# tx.net
KiCad netlist of a schematic drawn in Altium Designer
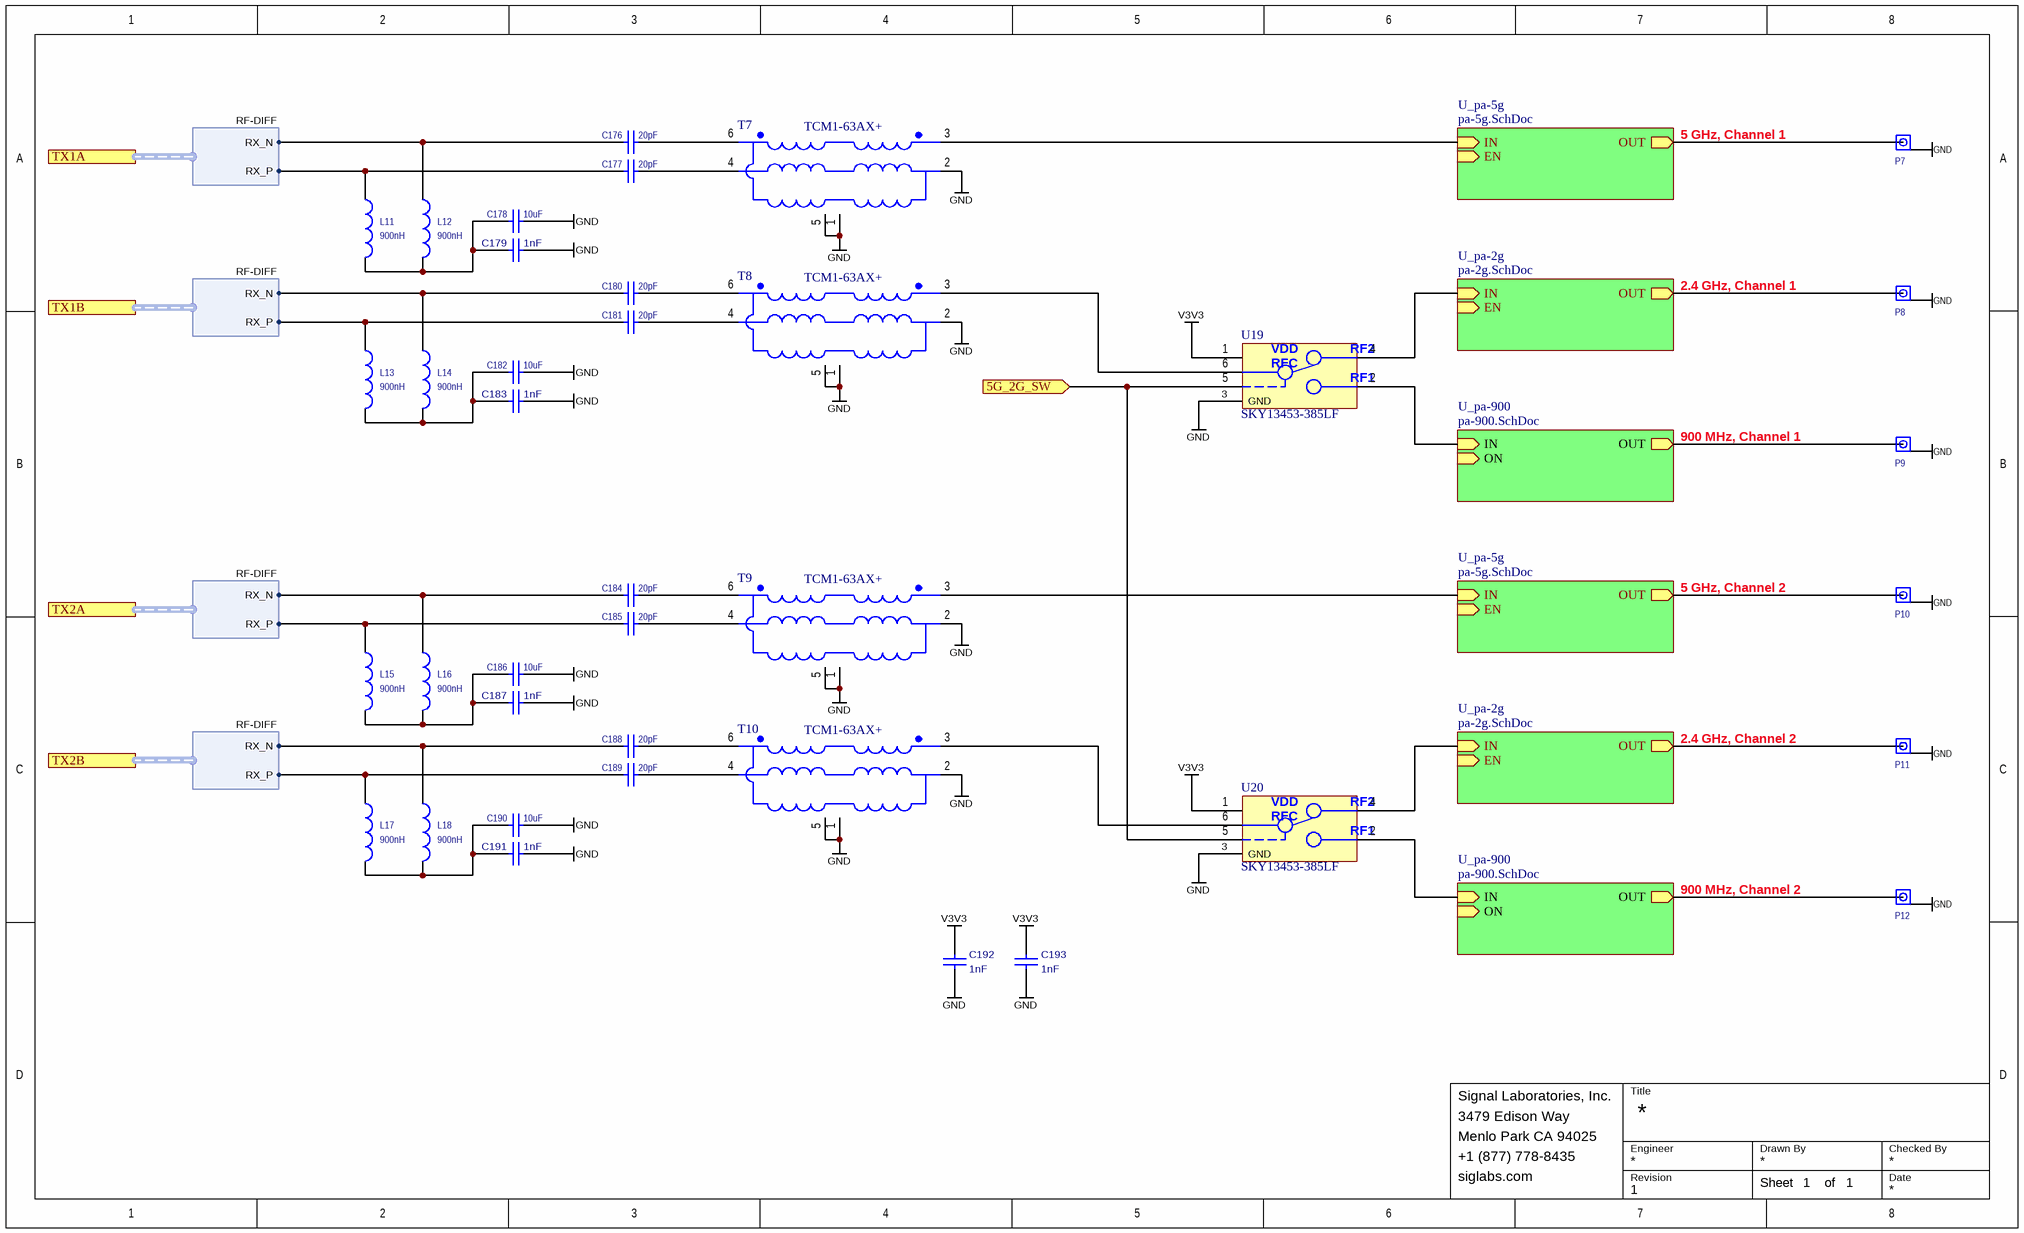
[diagram p0: tx.SchDoc]

(export (version "E")
  (design (tool "Eeschema 10.0.6"))
  (components
    (comp (ref "C176")
      (value "20pF")
      (footprint "generic:0402")
      (description "Ceramic Capacitor 20pF ±1% 50V NP0 0402")
      (fields (field (name "VOLTAGE") "50V") (field (name "MANUFACTURER") "Kemet"))
      (libsource (lib "PopRock") (part "CAP 0402"))
    )
    (comp (ref "C177")
      (value "20pF")
      (footprint "generic:0402")
      (description "Ceramic Capacitor 20pF ±1% 50V NP0 0402")
      (fields (field (name "VOLTAGE") "50V") (field (name "MANUFACTURER") "Kemet"))
      (libsource (lib "PopRock") (part "CAP 0402"))
    )
    (comp (ref "C178")
      (value "10uF")
      (footprint "generic:0603")
      (description "Ceramic Capacitor 10uF ±20% 25V X5R 0603")
      (fields (field (name "MANUFACTURER") "Samsung") (field (name "VOLTAGE") "25V"))
      (libsource (lib "generic") (part "CAP 0603"))
    )
    (comp (ref "C179")
      (value "1nF")
      (footprint "CAPC160X80X90L20N")
      (description "Ceramic Capacitor 1nF ±10% 50V X7R 0402")
      (fields (field (name "MANUFACTURER") "Vishay") (field (name "TOLERANCE") "±10%"))
      (libsource (lib "capacitors") (part "CAP"))
    )
    (comp (ref "C180")
      (value "20pF")
      (footprint "generic:0402")
      (description "Ceramic Capacitor 20pF ±1% 50V NP0 0402")
      (fields (field (name "VOLTAGE") "50V") (field (name "MANUFACTURER") "Kemet"))
      (libsource (lib "PopRock") (part "CAP 0402"))
    )
    (comp (ref "C181")
      (value "20pF")
      (footprint "generic:0402")
      (description "Ceramic Capacitor 20pF ±1% 50V NP0 0402")
      (fields (field (name "VOLTAGE") "50V") (field (name "MANUFACTURER") "Kemet"))
      (libsource (lib "PopRock") (part "CAP 0402"))
    )
    (comp (ref "C182")
      (value "10uF")
      (footprint "generic:0603")
      (description "Ceramic Capacitor 10uF ±20% 25V X5R 0603")
      (fields (field (name "MANUFACTURER") "Samsung") (field (name "VOLTAGE") "25V"))
      (libsource (lib "generic") (part "CAP 0603"))
    )
    (comp (ref "C183")
      (value "1nF")
      (footprint "CAPC160X80X90L20N")
      (description "Ceramic Capacitor 1nF ±10% 50V X7R 0402")
      (fields (field (name "MANUFACTURER") "Vishay") (field (name "TOLERANCE") "±10%"))
      (libsource (lib "capacitors") (part "CAP"))
    )
    (comp (ref "C184")
      (value "20pF")
      (footprint "generic:0402")
      (description "Ceramic Capacitor 20pF ±1% 50V NP0 0402")
      (fields (field (name "VOLTAGE") "50V") (field (name "MANUFACTURER") "Kemet"))
      (libsource (lib "PopRock") (part "CAP 0402"))
    )
    (comp (ref "C185")
      (value "20pF")
      (footprint "generic:0402")
      (description "Ceramic Capacitor 20pF ±1% 50V NP0 0402")
      (fields (field (name "VOLTAGE") "50V") (field (name "MANUFACTURER") "Kemet"))
      (libsource (lib "PopRock") (part "CAP 0402"))
    )
    (comp (ref "C186")
      (value "10uF")
      (footprint "generic:0603")
      (description "Ceramic Capacitor 10uF ±20% 25V X5R 0603")
      (fields (field (name "MANUFACTURER") "Samsung") (field (name "VOLTAGE") "25V"))
      (libsource (lib "generic") (part "CAP 0603"))
    )
    (comp (ref "C187")
      (value "1nF")
      (footprint "CAPC160X80X90L20N")
      (description "Ceramic Capacitor 1nF ±10% 50V X7R 0402")
      (fields (field (name "MANUFACTURER") "Vishay") (field (name "TOLERANCE") "±10%"))
      (libsource (lib "capacitors") (part "CAP"))
    )
    (comp (ref "C188")
      (value "20pF")
      (footprint "generic:0402")
      (description "Ceramic Capacitor 20pF ±1% 50V NP0 0402")
      (fields (field (name "VOLTAGE") "50V") (field (name "MANUFACTURER") "Kemet"))
      (libsource (lib "PopRock") (part "CAP 0402"))
    )
    (comp (ref "C189")
      (value "20pF")
      (footprint "generic:0402")
      (description "Ceramic Capacitor 20pF ±1% 50V NP0 0402")
      (fields (field (name "VOLTAGE") "50V") (field (name "MANUFACTURER") "Kemet"))
      (libsource (lib "PopRock") (part "CAP 0402"))
    )
    (comp (ref "C190")
      (value "10uF")
      (footprint "generic:0603")
      (description "Ceramic Capacitor 10uF ±20% 25V X5R 0603")
      (fields (field (name "MANUFACTURER") "Samsung") (field (name "VOLTAGE") "25V"))
      (libsource (lib "generic") (part "CAP 0603"))
    )
    (comp (ref "C191")
      (value "1nF")
      (footprint "CAPC160X80X90L20N")
      (description "Ceramic Capacitor 1nF ±10% 50V X7R 0402")
      (fields (field (name "MANUFACTURER") "Vishay") (field (name "TOLERANCE") "±10%"))
      (libsource (lib "capacitors") (part "CAP"))
    )
    (comp (ref "C192")
      (value "1nF")
      (footprint "CAPC160X80X90L20N")
      (description "Ceramic Capacitor 1nF ±10% 50V X7R 0402")
      (fields (field (name "MANUFACTURER") "Vishay") (field (name "TOLERANCE") "±10%"))
      (libsource (lib "capacitors") (part "CAP"))
    )
    (comp (ref "C193")
      (value "1nF")
      (footprint "CAPC160X80X90L20N")
      (description "Ceramic Capacitor 1nF ±10% 50V X7R 0402")
      (fields (field (name "MANUFACTURER") "Vishay") (field (name "TOLERANCE") "±10%"))
      (libsource (lib "capacitors") (part "CAP"))
    )
    (comp (ref "L11")
      (value "900nH")
      (footprint "coilcraft:COILCRAFT_1008AF")
      (description "Chip Inductor 900nH ±5% 1008")
      (fields (field (name "MANUFACTURER") "Coilcraft") (field (name "TOLERANCE") "±5%"))
      (libsource (lib "generic") (part "INDUCTOR"))
    )
    (comp (ref "L12")
      (value "900nH")
      (footprint "coilcraft:COILCRAFT_1008AF")
      (description "Chip Inductor 900nH ±5% 1008")
      (fields (field (name "MANUFACTURER") "Coilcraft") (field (name "TOLERANCE") "±5%"))
      (libsource (lib "generic") (part "INDUCTOR"))
    )
    (comp (ref "L13")
      (value "900nH")
      (footprint "coilcraft:COILCRAFT_1008AF")
      (description "Chip Inductor 900nH ±5% 1008")
      (fields (field (name "MANUFACTURER") "Coilcraft") (field (name "TOLERANCE") "±5%"))
      (libsource (lib "generic") (part "INDUCTOR"))
    )
    (comp (ref "L14")
      (value "900nH")
      (footprint "coilcraft:COILCRAFT_1008AF")
      (description "Chip Inductor 900nH ±5% 1008")
      (fields (field (name "MANUFACTURER") "Coilcraft") (field (name "TOLERANCE") "±5%"))
      (libsource (lib "generic") (part "INDUCTOR"))
    )
    (comp (ref "L15")
      (value "900nH")
      (footprint "coilcraft:COILCRAFT_1008AF")
      (description "Chip Inductor 900nH ±5% 1008")
      (fields (field (name "MANUFACTURER") "Coilcraft") (field (name "TOLERANCE") "±5%"))
      (libsource (lib "generic") (part "INDUCTOR"))
    )
    (comp (ref "L16")
      (value "900nH")
      (footprint "coilcraft:COILCRAFT_1008AF")
      (description "Chip Inductor 900nH ±5% 1008")
      (fields (field (name "MANUFACTURER") "Coilcraft") (field (name "TOLERANCE") "±5%"))
      (libsource (lib "generic") (part "INDUCTOR"))
    )
    (comp (ref "L17")
      (value "900nH")
      (footprint "coilcraft:COILCRAFT_1008AF")
      (description "Chip Inductor 900nH ±5% 1008")
      (fields (field (name "MANUFACTURER") "Coilcraft") (field (name "TOLERANCE") "±5%"))
      (libsource (lib "generic") (part "INDUCTOR"))
    )
    (comp (ref "L18")
      (value "900nH")
      (footprint "coilcraft:COILCRAFT_1008AF")
      (description "Chip Inductor 900nH ±5% 1008")
      (fields (field (name "MANUFACTURER") "Coilcraft") (field (name "TOLERANCE") "±5%"))
      (libsource (lib "generic") (part "INDUCTOR"))
    )
    (comp (ref "P7")
      (value "U.FL-R-SMT(10)")
      (footprint "U.FL-R-SMT(10)")
      (description "Ultra Miniature Coaxial Jack, 50 Ohms")
      (fields (field (name "MANUFACTURER") "Hirose"))
      (libsource (lib "hirose") (part "U.FL-R-SMT(10)"))
    )
    (comp (ref "P8")
      (value "U.FL-R-SMT(10)")
      (footprint "U.FL-R-SMT(10)")
      (description "Ultra Miniature Coaxial Jack, 50 Ohms")
      (fields (field (name "MANUFACTURER") "Hirose"))
      (libsource (lib "hirose") (part "U.FL-R-SMT(10)"))
    )
    (comp (ref "P9")
      (value "U.FL-R-SMT(10)")
      (footprint "U.FL-R-SMT(10)")
      (description "Ultra Miniature Coaxial Jack, 50 Ohms")
      (fields (field (name "MANUFACTURER") "Hirose"))
      (libsource (lib "hirose") (part "U.FL-R-SMT(10)"))
    )
    (comp (ref "P10")
      (value "U.FL-R-SMT(10)")
      (footprint "U.FL-R-SMT(10)")
      (description "Ultra Miniature Coaxial Jack, 50 Ohms")
      (fields (field (name "MANUFACTURER") "Hirose"))
      (libsource (lib "hirose") (part "U.FL-R-SMT(10)"))
    )
    (comp (ref "P11")
      (value "U.FL-R-SMT(10)")
      (footprint "U.FL-R-SMT(10)")
      (description "Ultra Miniature Coaxial Jack, 50 Ohms")
      (fields (field (name "MANUFACTURER") "Hirose"))
      (libsource (lib "hirose") (part "U.FL-R-SMT(10)"))
    )
    (comp (ref "P12")
      (value "U.FL-R-SMT(10)")
      (footprint "U.FL-R-SMT(10)")
      (description "Ultra Miniature Coaxial Jack, 50 Ohms")
      (fields (field (name "MANUFACTURER") "Hirose"))
      (libsource (lib "hirose") (part "U.FL-R-SMT(10)"))
    )
    (comp (ref "T7")
      (value "TCM1-63AX+")
      (footprint "TCM1-63AX+")
      (description "RF Transformer 10-6000KHz")
      (fields (field (name "MANUFACTURER") "Mini-Circuits"))
      (libsource (lib "Mini-Circuits") (part "TCM1-63AX+"))
    )
    (comp (ref "T8")
      (value "TCM1-63AX+")
      (footprint "TCM1-63AX+")
      (description "RF Transformer 10-6000KHz")
      (fields (field (name "MANUFACTURER") "Mini-Circuits"))
      (libsource (lib "Mini-Circuits") (part "TCM1-63AX+"))
    )
    (comp (ref "T9")
      (value "TCM1-63AX+")
      (footprint "TCM1-63AX+")
      (description "RF Transformer 10-6000KHz")
      (fields (field (name "MANUFACTURER") "Mini-Circuits"))
      (libsource (lib "Mini-Circuits") (part "TCM1-63AX+"))
    )
    (comp (ref "T10")
      (value "TCM1-63AX+")
      (footprint "TCM1-63AX+")
      (description "RF Transformer 10-6000KHz")
      (fields (field (name "MANUFACTURER") "Mini-Circuits"))
      (libsource (lib "Mini-Circuits") (part "TCM1-63AX+"))
    )
    (comp (ref "U19")
      (value "SKY13453-385LF")
      (footprint "SKY13453-385LF")
      (description "0.01 MHz-6.0 GHz RF SPDT Switch")
      (fields (field (name "MANUFACTURER") "Skyworks"))
      (libsource (lib "skyworks") (part "SKY13453-385LF"))
    )
    (comp (ref "U20")
      (value "SKY13453-385LF")
      (footprint "SKY13453-385LF")
      (description "0.01 MHz-6.0 GHz RF SPDT Switch")
      (fields (field (name "MANUFACTURER") "Skyworks"))
      (libsource (lib "skyworks") (part "SKY13453-385LF"))
    )
  )
  (nets
    (net (code "2") (name "/5G_2G_SW") (class "Default")
      (node (ref "U19") (pin "5") (pinfunction "CTL_5") (pintype "passive"))
      (node (ref "U20") (pin "5") (pinfunction "CTL_5") (pintype "passive"))
    )
    (net (code "7") (name "/IN") (class "Default")
      (node (ref "U20") (pin "4") (pinfunction "RF2_4") (pintype "passive"))
    )
    (net (code "8") (name "/IN_1") (class "Default")
      (node (ref "U20") (pin "2") (pinfunction "RF1_2") (pintype "passive"))
    )
    (net (code "9") (name "/IN_2") (class "Default")
      (node (ref "T7") (pin "3") (pinfunction "3_3") (pintype "passive"))
    )
    (net (code "10") (name "/IN_3") (class "Default")
      (node (ref "U19") (pin "4") (pinfunction "RF2_4") (pintype "passive"))
    )
    (net (code "11") (name "/IN_4") (class "Default")
      (node (ref "U19") (pin "2") (pinfunction "RF1_2") (pintype "passive"))
    )
    (net (code "12") (name "/IN_5") (class "Default")
      (node (ref "T9") (pin "3") (pinfunction "3_3") (pintype "passive"))
    )
    (net (code "15") (name "/OUT") (class "Default")
      (node (ref "P11") (pin "1") (pinfunction "RF_1") (pintype "passive"))
    )
    (net (code "16") (name "/OUT_1") (class "Default")
      (node (ref "P12") (pin "1") (pinfunction "RF_1") (pintype "passive"))
    )
    (net (code "17") (name "/OUT_2") (class "Default")
      (node (ref "P10") (pin "1") (pinfunction "RF_1") (pintype "passive"))
    )
    (net (code "18") (name "/OUT_3") (class "Default")
      (node (ref "P9") (pin "1") (pinfunction "RF_1") (pintype "passive"))
    )
    (net (code "19") (name "/OUT_4") (class "Default")
      (node (ref "P8") (pin "1") (pinfunction "RF_1") (pintype "passive"))
    )
    (net (code "20") (name "/OUT_5") (class "Default")
      (node (ref "P7") (pin "1") (pinfunction "RF_1") (pintype "passive"))
    )
    (net (code "22") (name "GND") (class "Default")
      (node (ref "C178") (pin "1") (pinfunction "1_1") (pintype "passive"))
      (node (ref "C179") (pin "2") (pinfunction "2_2") (pintype "passive"))
      (node (ref "C182") (pin "1") (pinfunction "1_1") (pintype "passive"))
      (node (ref "C183") (pin "2") (pinfunction "2_2") (pintype "passive"))
      (node (ref "C186") (pin "1") (pinfunction "1_1") (pintype "passive"))
      (node (ref "C187") (pin "2") (pinfunction "2_2") (pintype "passive"))
      (node (ref "C190") (pin "1") (pinfunction "1_1") (pintype "passive"))
      (node (ref "C191") (pin "2") (pinfunction "2_2") (pintype "passive"))
      (node (ref "C192") (pin "1") (pinfunction "1_1") (pintype "passive"))
      (node (ref "C193") (pin "1") (pinfunction "1_1") (pintype "passive"))
      (node (ref "P10") (pin "2") (pinfunction "GND_2") (pintype "passive"))
      (node (ref "P11") (pin "2") (pinfunction "GND_2") (pintype "passive"))
      (node (ref "P12") (pin "2") (pinfunction "GND_2") (pintype "passive"))
      (node (ref "P7") (pin "2") (pinfunction "GND_2") (pintype "passive"))
      (node (ref "P8") (pin "2") (pinfunction "GND_2") (pintype "passive"))
      (node (ref "P9") (pin "2") (pinfunction "GND_2") (pintype "passive"))
      (node (ref "T10") (pin "1") (pinfunction "1_1") (pintype "passive"))
      (node (ref "T10") (pin "2") (pinfunction "2_2") (pintype "passive"))
      (node (ref "T10") (pin "5") (pinfunction "5_5") (pintype "passive"))
      (node (ref "T7") (pin "1") (pinfunction "1_1") (pintype "passive"))
      (node (ref "T7") (pin "2") (pinfunction "2_2") (pintype "passive"))
      (node (ref "T7") (pin "5") (pinfunction "5_5") (pintype "passive"))
      (node (ref "T8") (pin "1") (pinfunction "1_1") (pintype "passive"))
      (node (ref "T8") (pin "2") (pinfunction "2_2") (pintype "passive"))
      (node (ref "T8") (pin "5") (pinfunction "5_5") (pintype "passive"))
      (node (ref "T9") (pin "1") (pinfunction "1_1") (pintype "passive"))
      (node (ref "T9") (pin "2") (pinfunction "2_2") (pintype "passive"))
      (node (ref "T9") (pin "5") (pinfunction "5_5") (pintype "passive"))
      (node (ref "U19") (pin "3") (pinfunction "GND_3") (pintype "passive"))
      (node (ref "U20") (pin "3") (pinfunction "GND_3") (pintype "passive"))
    )
    (net (code "23") (name "Net-(C176-Pad1)") (class "Default")
      (node (ref "C176") (pin "1") (pinfunction "1_1") (pintype "passive"))
      (node (ref "L12") (pin "1") (pinfunction "1_1") (pintype "passive"))
    )
    (net (code "24") (name "Net-(C176-Pad2)") (class "Default")
      (node (ref "C176") (pin "2") (pinfunction "2_2") (pintype "passive"))
      (node (ref "T7") (pin "6") (pinfunction "6_6") (pintype "passive"))
    )
    (net (code "25") (name "Net-(C177-Pad1)") (class "Default")
      (node (ref "C177") (pin "1") (pinfunction "1_1") (pintype "passive"))
      (node (ref "L11") (pin "1") (pinfunction "1_1") (pintype "passive"))
    )
    (net (code "26") (name "Net-(C177-Pad2)") (class "Default")
      (node (ref "C177") (pin "2") (pinfunction "2_2") (pintype "passive"))
      (node (ref "T7") (pin "4") (pinfunction "4_4") (pintype "passive"))
    )
    (net (code "27") (name "Net-(C178-Pad2)") (class "Default")
      (node (ref "C178") (pin "2") (pinfunction "2_2") (pintype "passive"))
      (node (ref "C179") (pin "1") (pinfunction "1_1") (pintype "passive"))
      (node (ref "L11") (pin "2") (pinfunction "2_2") (pintype "passive"))
      (node (ref "L12") (pin "2") (pinfunction "2_2") (pintype "passive"))
    )
    (net (code "28") (name "Net-(C180-Pad1)") (class "Default")
      (node (ref "C180") (pin "1") (pinfunction "1_1") (pintype "passive"))
      (node (ref "L14") (pin "1") (pinfunction "1_1") (pintype "passive"))
    )
    (net (code "29") (name "Net-(C180-Pad2)") (class "Default")
      (node (ref "C180") (pin "2") (pinfunction "2_2") (pintype "passive"))
      (node (ref "T8") (pin "6") (pinfunction "6_6") (pintype "passive"))
    )
    (net (code "30") (name "Net-(C181-Pad1)") (class "Default")
      (node (ref "C181") (pin "1") (pinfunction "1_1") (pintype "passive"))
      (node (ref "L13") (pin "1") (pinfunction "1_1") (pintype "passive"))
    )
    (net (code "31") (name "Net-(C181-Pad2)") (class "Default")
      (node (ref "C181") (pin "2") (pinfunction "2_2") (pintype "passive"))
      (node (ref "T8") (pin "4") (pinfunction "4_4") (pintype "passive"))
    )
    (net (code "32") (name "Net-(C182-Pad2)") (class "Default")
      (node (ref "C182") (pin "2") (pinfunction "2_2") (pintype "passive"))
      (node (ref "C183") (pin "1") (pinfunction "1_1") (pintype "passive"))
      (node (ref "L13") (pin "2") (pinfunction "2_2") (pintype "passive"))
      (node (ref "L14") (pin "2") (pinfunction "2_2") (pintype "passive"))
    )
    (net (code "33") (name "Net-(C184-Pad1)") (class "Default")
      (node (ref "C184") (pin "1") (pinfunction "1_1") (pintype "passive"))
      (node (ref "L16") (pin "1") (pinfunction "1_1") (pintype "passive"))
    )
    (net (code "34") (name "Net-(C184-Pad2)") (class "Default")
      (node (ref "C184") (pin "2") (pinfunction "2_2") (pintype "passive"))
      (node (ref "T9") (pin "6") (pinfunction "6_6") (pintype "passive"))
    )
    (net (code "35") (name "Net-(C185-Pad1)") (class "Default")
      (node (ref "C185") (pin "1") (pinfunction "1_1") (pintype "passive"))
      (node (ref "L15") (pin "1") (pinfunction "1_1") (pintype "passive"))
    )
    (net (code "36") (name "Net-(C185-Pad2)") (class "Default")
      (node (ref "C185") (pin "2") (pinfunction "2_2") (pintype "passive"))
      (node (ref "T9") (pin "4") (pinfunction "4_4") (pintype "passive"))
    )
    (net (code "37") (name "Net-(C186-Pad2)") (class "Default")
      (node (ref "C186") (pin "2") (pinfunction "2_2") (pintype "passive"))
      (node (ref "C187") (pin "1") (pinfunction "1_1") (pintype "passive"))
      (node (ref "L15") (pin "2") (pinfunction "2_2") (pintype "passive"))
      (node (ref "L16") (pin "2") (pinfunction "2_2") (pintype "passive"))
    )
    (net (code "38") (name "Net-(C188-Pad1)") (class "Default")
      (node (ref "C188") (pin "1") (pinfunction "1_1") (pintype "passive"))
      (node (ref "L18") (pin "1") (pinfunction "1_1") (pintype "passive"))
    )
    (net (code "39") (name "Net-(C188-Pad2)") (class "Default")
      (node (ref "C188") (pin "2") (pinfunction "2_2") (pintype "passive"))
      (node (ref "T10") (pin "6") (pinfunction "6_6") (pintype "passive"))
    )
    (net (code "40") (name "Net-(C189-Pad1)") (class "Default")
      (node (ref "C189") (pin "1") (pinfunction "1_1") (pintype "passive"))
      (node (ref "L17") (pin "1") (pinfunction "1_1") (pintype "passive"))
    )
    (net (code "41") (name "Net-(C189-Pad2)") (class "Default")
      (node (ref "C189") (pin "2") (pinfunction "2_2") (pintype "passive"))
      (node (ref "T10") (pin "4") (pinfunction "4_4") (pintype "passive"))
    )
    (net (code "42") (name "Net-(C190-Pad2)") (class "Default")
      (node (ref "C190") (pin "2") (pinfunction "2_2") (pintype "passive"))
      (node (ref "C191") (pin "1") (pinfunction "1_1") (pintype "passive"))
      (node (ref "L17") (pin "2") (pinfunction "2_2") (pintype "passive"))
      (node (ref "L18") (pin "2") (pinfunction "2_2") (pintype "passive"))
    )
    (net (code "43") (name "Net-(U19-J1)") (class "Default")
      (node (ref "T8") (pin "3") (pinfunction "3_3") (pintype "passive"))
      (node (ref "U19") (pin "6") (pinfunction "J1_6") (pintype "passive"))
    )
    (net (code "44") (name "Net-(U20-J1)") (class "Default")
      (node (ref "T10") (pin "3") (pinfunction "3_3") (pintype "passive"))
      (node (ref "U20") (pin "6") (pinfunction "J1_6") (pintype "passive"))
    )
    (net (code "45") (name "V3V3") (class "Default")
      (node (ref "C192") (pin "2") (pinfunction "2_2") (pintype "passive"))
      (node (ref "C193") (pin "2") (pinfunction "2_2") (pintype "passive"))
      (node (ref "U19") (pin "1") (pinfunction "VDD_1") (pintype "passive"))
      (node (ref "U20") (pin "1") (pinfunction "VDD_1") (pintype "passive"))
    )
  )
)
